# crawler2body.net
KiCad netlist of a schematic drawn in EAGLE
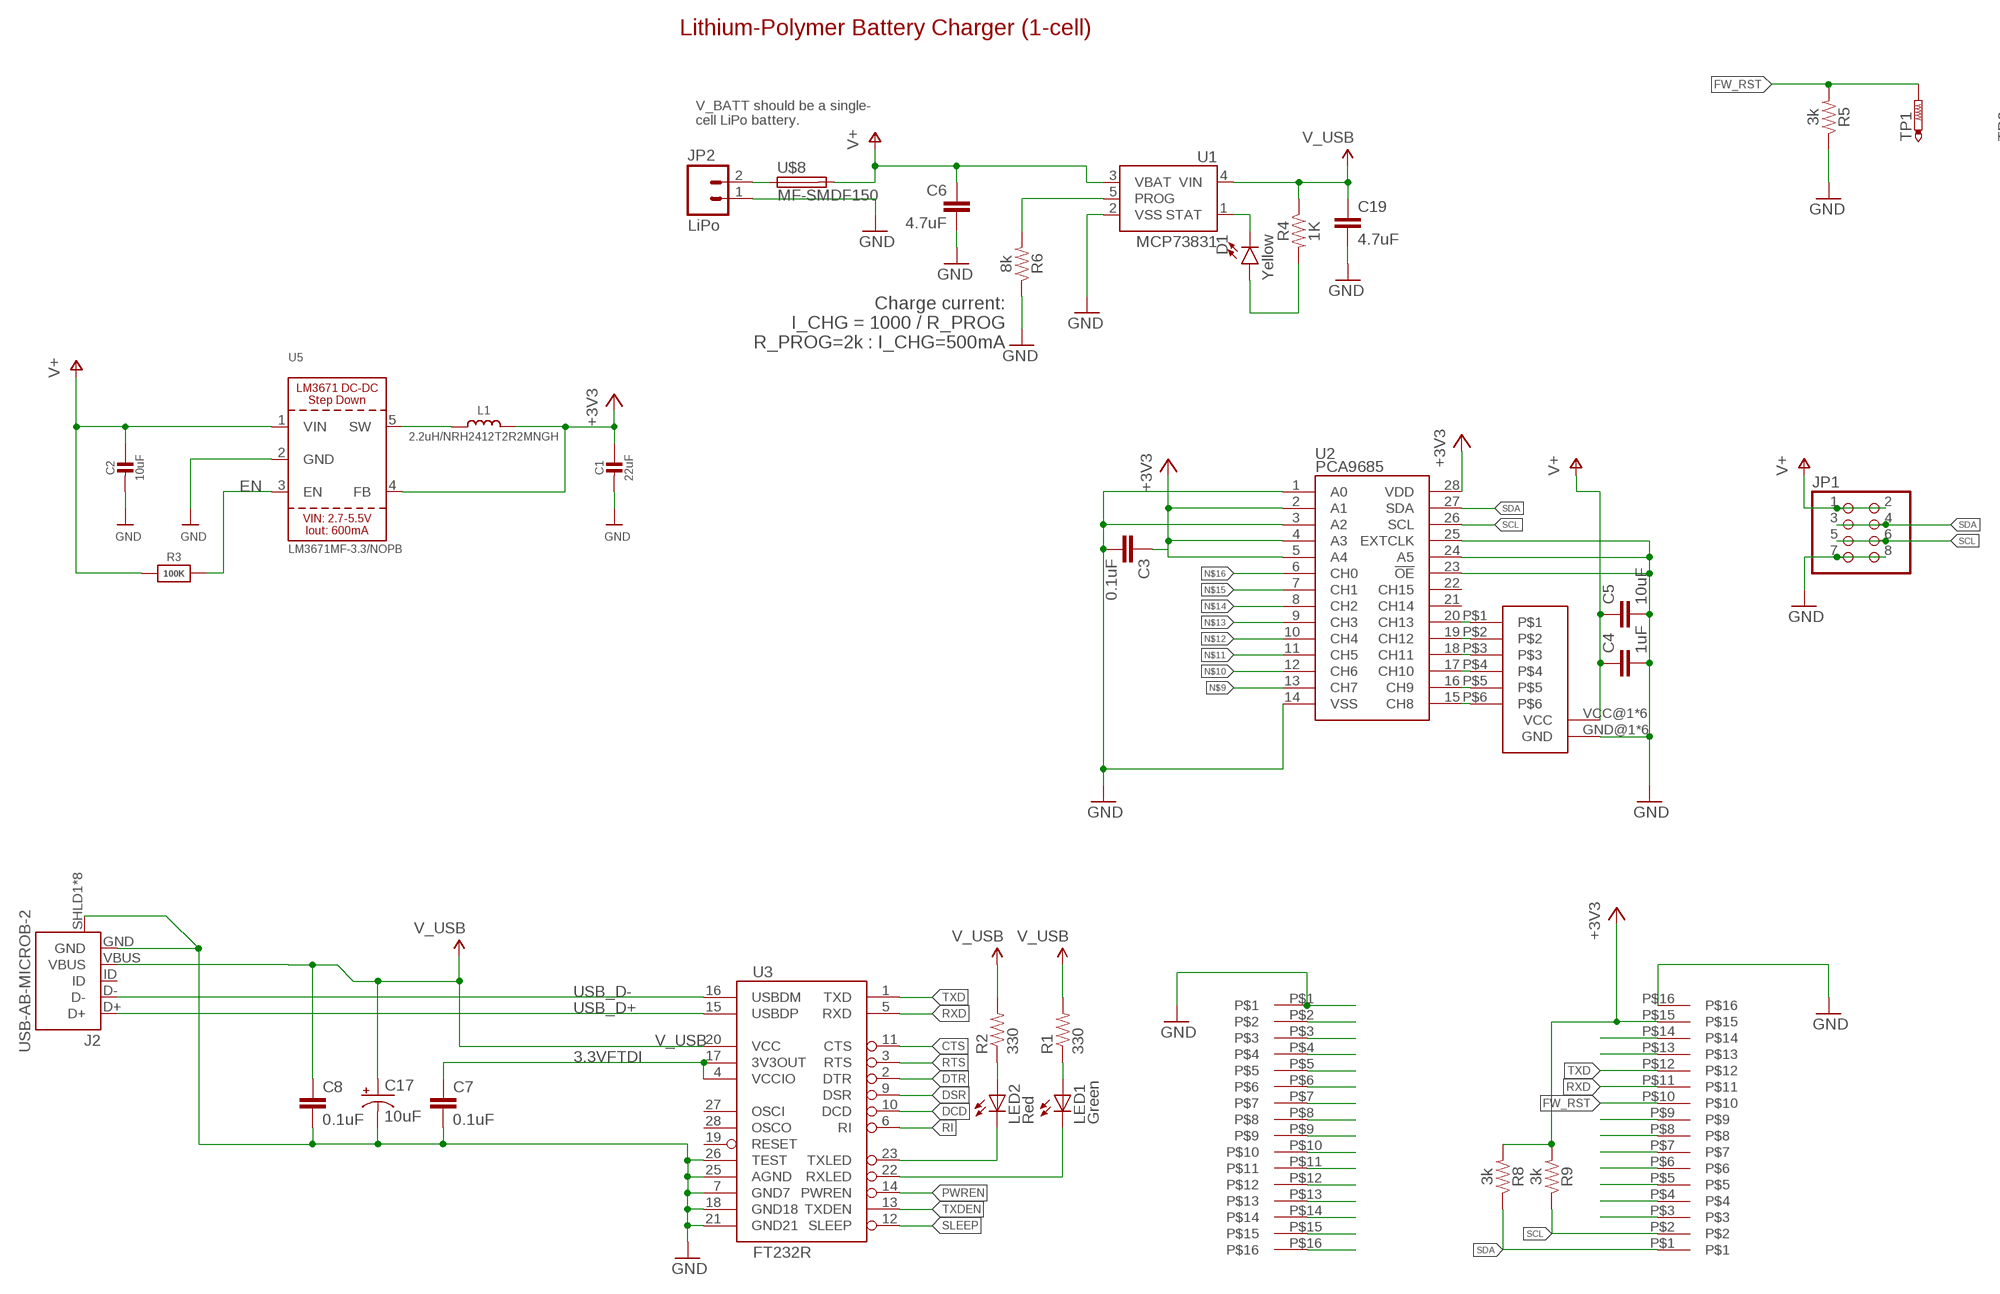
[diagram p0: schematic, sheet 1, part 1 of 2]
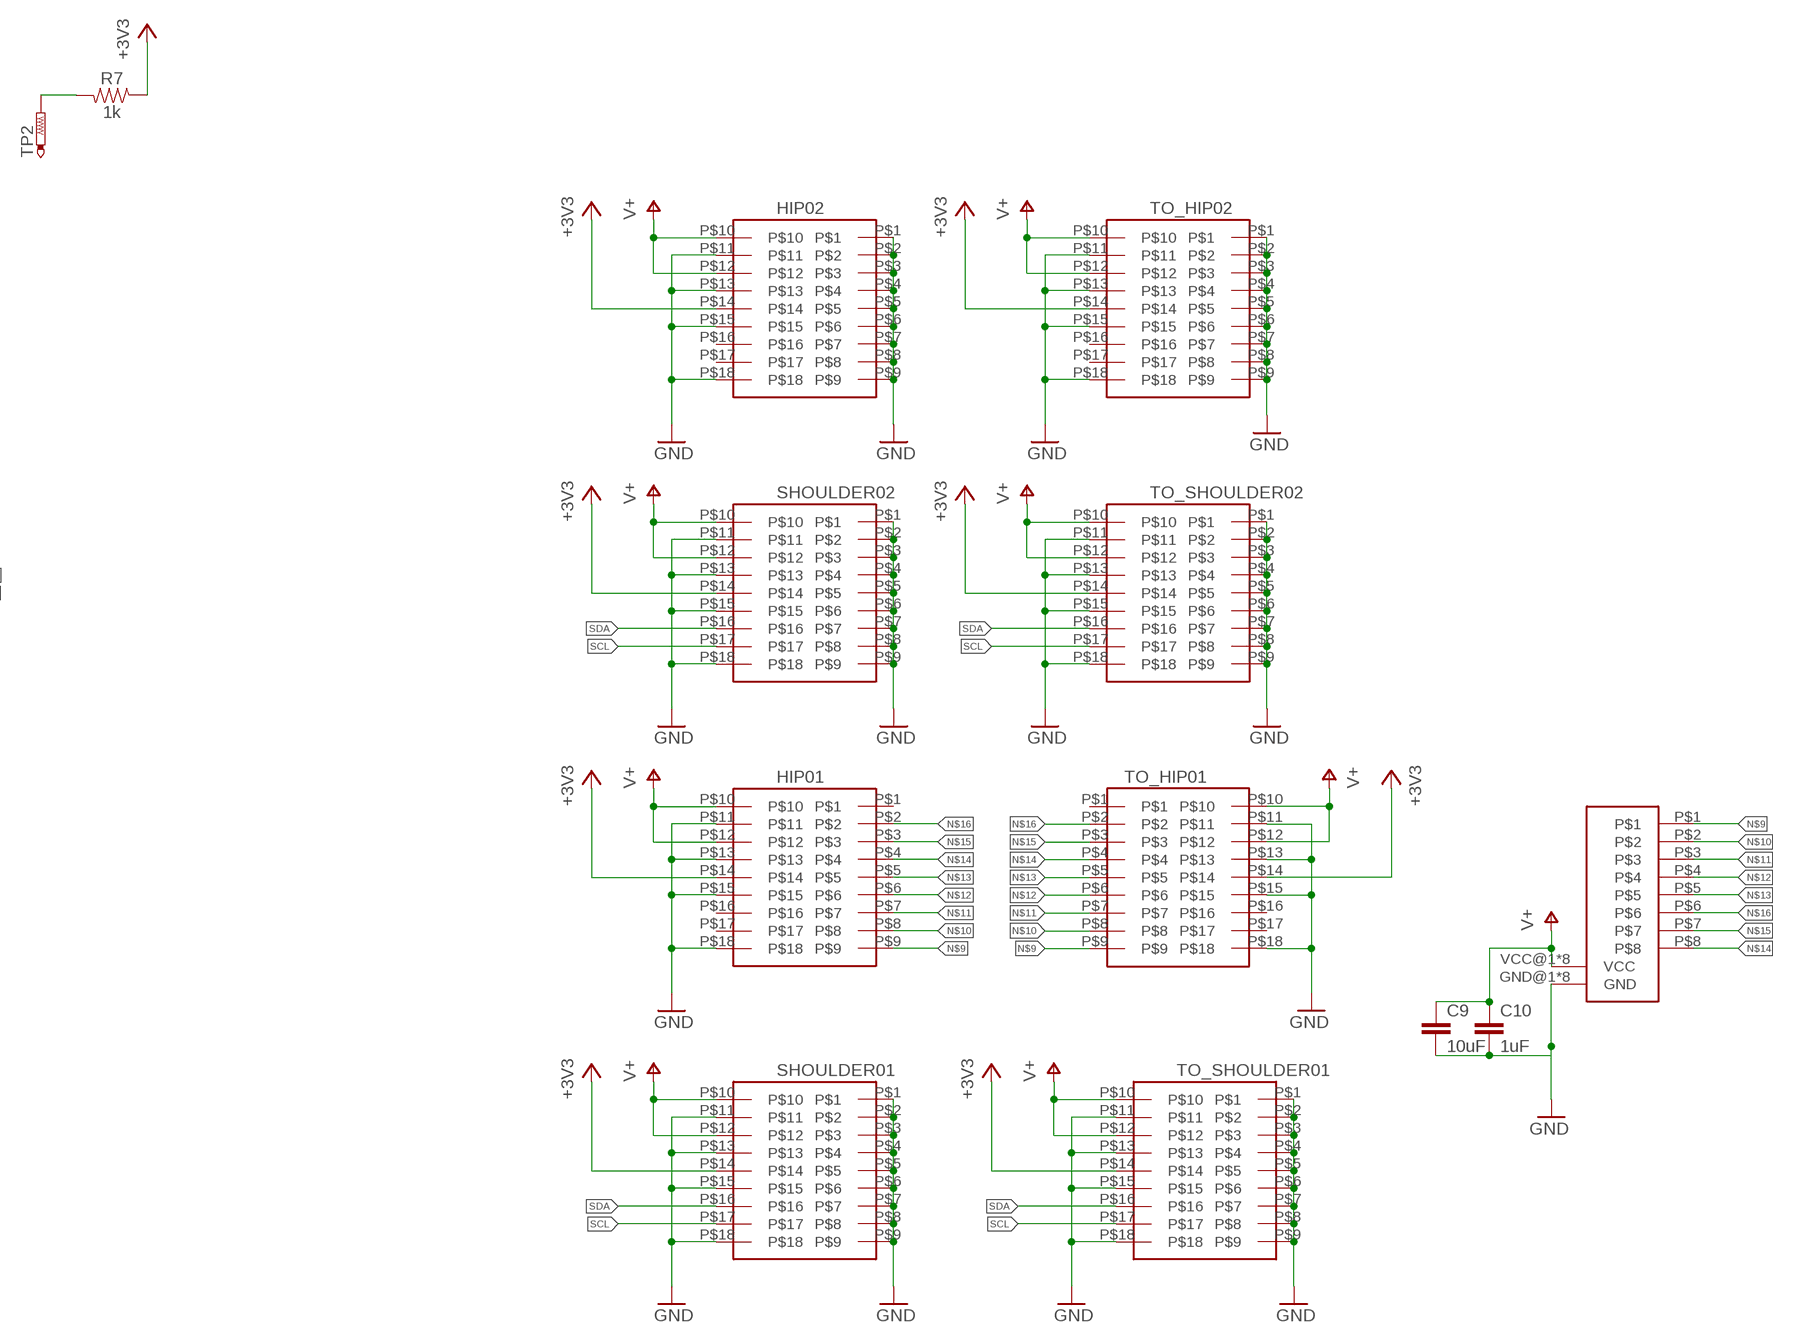
[diagram p1: schematic, sheet 1, part 2 of 2]

(export (version "E")
  (design (tool "Eeschema 10.0.6"))
  (components
    (comp (ref "C1")
      (value "22uF")
      (footprint "eagle-import:0805-NO")
      (libsource (lib "eagle-import") (part "CAP_CERAMIC0805-NOOUTLINE"))
    )
    (comp (ref "C2")
      (value "10uF")
      (footprint "eagle-import:0805-NO")
      (libsource (lib "eagle-import") (part "CAP_CERAMIC0805-NOOUTLINE"))
    )
    (comp (ref "C3")
      (value "0.1uF")
      (footprint "eagle-import:0603-CAP")
      (libsource (lib "eagle-import") (part "0.1UF-25V(+80/-20%)(0603)"))
    )
    (comp (ref "C4")
      (value "1uF")
      (footprint "eagle-import:C1210")
      (libsource (lib "eagle-import") (part "C-EUC1210"))
    )
    (comp (ref "C5")
      (value "10uF")
      (footprint "eagle-import:C1210")
      (libsource (lib "eagle-import") (part "C-EUC1210"))
    )
    (comp (ref "C6")
      (value "4.7uF")
      (footprint "eagle-import:0603")
      (libsource (lib "eagle-import") (part "4.7UF0603"))
    )
    (comp (ref "C7")
      (value "0.1uF")
      (footprint "eagle-import:0603-CAP")
      (libsource (lib "eagle-import") (part "0.1UF-25V(+80/-20%)(0603)"))
    )
    (comp (ref "C8")
      (value "0.1uF")
      (footprint "eagle-import:0603-CAP")
      (libsource (lib "eagle-import") (part "0.1UF-25V(+80/-20%)(0603)"))
    )
    (comp (ref "C9")
      (value "10uF")
      (footprint "eagle-import:C1210")
      (libsource (lib "eagle-import") (part "C-EUC1210"))
    )
    (comp (ref "C10")
      (value "1uF")
      (footprint "eagle-import:C1210")
      (libsource (lib "eagle-import") (part "C-EUC1210"))
    )
    (comp (ref "C17")
      (value "10uF")
      (footprint "eagle-import:EIA3216")
      (libsource (lib "eagle-import") (part "10UF-16V-10%(TANT)"))
    )
    (comp (ref "C19")
      (value "4.7uF")
      (footprint "eagle-import:0603")
      (libsource (lib "eagle-import") (part "4.7UF0603"))
    )
    (comp (ref "D1")
      (value "Yellow")
      (footprint "eagle-import:LED-0603")
      (libsource (lib "eagle-import") (part "LED-YELLOW0603"))
    )
    (comp (ref "HIP01")
      (value "BOARD2BOARD_SLOT")
      (footprint "eagle-import:BOARD2BOARD_SLOT")
      (libsource (lib "eagle-import") (part "BOARD2BOARD_SLOT"))
    )
    (comp (ref "HIP02")
      (value "BOARD2BOARD_SLOT")
      (footprint "eagle-import:BOARD2BOARD_SLOT")
      (libsource (lib "eagle-import") (part "BOARD2BOARD_SLOT"))
    )
    (comp (ref "J2")
      (value "USB-AB-MICROB-2")
      (footprint "eagle-import:USB-MICROB-10118194")
      (libsource (lib "eagle-import") (part "USB-AB-MICROB-2"))
    )
    (comp (ref "JP1")
      (value "PINHD-2X4")
      (footprint "eagle-import:2X04")
      (libsource (lib "eagle-import") (part "PINHD-2X4"))
    )
    (comp (ref "JP2")
      (value "LiPo")
      (footprint "eagle-import:JST-2-PTH-NS")
      (libsource (lib "eagle-import") (part "M02-JST-2-PTH-NO_SILK"))
    )
    (comp (ref "L1")
      (value "2.2uH/NRH2412T2R2MNGH")
      (footprint "eagle-import:INDUCTOR_TAIYOYUDEN_NRH2412T")
      (libsource (lib "eagle-import") (part "INDUCTORNRH2412T"))
    )
    (comp (ref "LED1")
      (value "Green")
      (footprint "eagle-import:LED-0603@1")
      (libsource (lib "eagle-import") (part "LED-GREEN0603"))
    )
    (comp (ref "LED2")
      (value "Red")
      (footprint "eagle-import:LED-0603@1")
      (libsource (lib "eagle-import") (part "LED-RED0603"))
    )
    (comp (ref "R1")
      (value "330")
      (footprint "eagle-import:0603-RES")
      (libsource (lib "eagle-import") (part "330OHM1/10W1%(0603)"))
    )
    (comp (ref "R2")
      (value "330")
      (footprint "eagle-import:0603-RES")
      (libsource (lib "eagle-import") (part "330OHM1/10W1%(0603)"))
    )
    (comp (ref "R3")
      (value "100K")
      (footprint "eagle-import:0805-NO")
      (libsource (lib "eagle-import") (part "RESISTOR0805_NOOUTLINE"))
    )
    (comp (ref "R4")
      (value "1K")
      (footprint "eagle-import:0603")
      (libsource (lib "eagle-import") (part "1KOHM-1/10W-1%(0603)"))
    )
    (comp (ref "R5")
      (value "3k")
      (footprint "eagle-import:0603")
      (libsource (lib "eagle-import") (part "2.0KOHM1/10W5%(0603)"))
    )
    (comp (ref "R6")
      (value "8k")
      (footprint "eagle-import:0603")
      (libsource (lib "eagle-import") (part "2.0KOHM1/10W5%(0603)"))
    )
    (comp (ref "R7")
      (value "1k")
      (footprint "eagle-import:0603")
      (libsource (lib "eagle-import") (part "2.0KOHM1/10W5%(0603)"))
    )
    (comp (ref "R8")
      (value "3k")
      (footprint "eagle-import:0603")
      (libsource (lib "eagle-import") (part "2.0KOHM1/10W5%(0603)"))
    )
    (comp (ref "R9")
      (value "3k")
      (footprint "eagle-import:0603")
      (libsource (lib "eagle-import") (part "2.0KOHM1/10W5%(0603)"))
    )
    (comp (ref "SHOULDER01")
      (value "BOARD2BOARD_SLOT")
      (footprint "eagle-import:BOARD2BOARD_SLOT")
      (libsource (lib "eagle-import") (part "BOARD2BOARD_SLOT"))
    )
    (comp (ref "SHOULDER02")
      (value "BOARD2BOARD_SLOT")
      (footprint "eagle-import:BOARD2BOARD_SLOT")
      (libsource (lib "eagle-import") (part "BOARD2BOARD_SLOT"))
    )
    (comp (ref "TO_HIP01")
      (value "BOARD2BOARD")
      (footprint "eagle-import:BOARD2BOARD")
      (libsource (lib "eagle-import") (part "BOARD2BOARD"))
    )
    (comp (ref "TO_HIP02")
      (value "BOARD2BOARD")
      (footprint "eagle-import:BOARD2BOARD")
      (libsource (lib "eagle-import") (part "BOARD2BOARD"))
    )
    (comp (ref "TO_SHOULDER01")
      (value "BOARD2BOARD")
      (footprint "eagle-import:BOARD2BOARD")
      (libsource (lib "eagle-import") (part "BOARD2BOARD"))
    )
    (comp (ref "TO_SHOULDER02")
      (value "BOARD2BOARD")
      (footprint "eagle-import:BOARD2BOARD")
      (libsource (lib "eagle-import") (part "BOARD2BOARD"))
    )
    (comp (ref "TP1")
      (value "PTR1TP15SQ")
      (footprint "eagle-import:TP15SQ")
      (libsource (lib "eagle-import") (part "PTR1TP15SQ"))
    )
    (comp (ref "TP2")
      (value "PTR1TP15SQ")
      (footprint "eagle-import:TP15SQ")
      (libsource (lib "eagle-import") (part "PTR1TP15SQ"))
    )
    (comp (ref "U$1")
      (value "SPLITPAC_OMEGA2")
      (footprint "eagle-import:SPLITTED_OMEGA2")
      (libsource (lib "eagle-import") (part "SPLITPAC_OMEGA2"))
    )
    (comp (ref "U$2")
      (value "SPLITPAC_OMEGA2")
      (footprint "eagle-import:SPLITTED_OMEGA2")
      (libsource (lib "eagle-import") (part "SPLITPAC_OMEGA2"))
    )
    (comp (ref "U$3")
      (value "RC8CHAN")
      (footprint "eagle-import:RC8CHAN")
      (libsource (lib "eagle-import") (part "RC8CHAN"))
    )
    (comp (ref "U$4")
      (value "RC6CHAN")
      (footprint "eagle-import:RC6CHAN")
      (libsource (lib "eagle-import") (part "RC6CHAN"))
    )
    (comp (ref "U$8")
      (value "MF-SMDF150")
      (footprint "eagle-import:MF-SMDF050")
      (libsource (lib "eagle-import") (part "MF-SMDF150"))
    )
    (comp (ref "U1")
      (value "MCP73831")
      (footprint "eagle-import:SOT23-5")
      (libsource (lib "eagle-import") (part "MCP73831"))
    )
    (comp (ref "U2")
      (value "PCA9685")
      (footprint "eagle-import:TSSOP-28_4MM")
      (libsource (lib "eagle-import") (part "PCA9685"))
    )
    (comp (ref "U3")
      (value "FT232R")
      (footprint "eagle-import:SSOP28DB")
      (libsource (lib "eagle-import") (part "FT232RLSSOP"))
    )
    (comp (ref "U5")
      (value "LM3671MF-3.3/NOPB")
      (footprint "eagle-import:SOT23-5")
      (libsource (lib "eagle-import") (part "VREG_LM3671"))
    )
  )
  (nets
    (net (code "1") (name "+3V3") (class "Default")
      (node (ref "C1") (pin "1") (pinfunction "1_1") (pintype "passive"))
      (node (ref "C3") (pin "1") (pinfunction "1_1") (pintype "passive"))
      (node (ref "HIP01") (pin "P$14") (pinfunction "P$14_P$14") (pintype "bidirectional"))
      (node (ref "HIP02") (pin "P$14") (pinfunction "P$14_P$14") (pintype "bidirectional"))
      (node (ref "L1") (pin "2") (pinfunction "2_2") (pintype "passive"))
      (node (ref "R7") (pin "1") (pinfunction "1_1") (pintype "passive"))
      (node (ref "R8") (pin "2") (pinfunction "2_2") (pintype "passive"))
      (node (ref "R9") (pin "2") (pinfunction "2_2") (pintype "passive"))
      (node (ref "SHOULDER01") (pin "P$14") (pinfunction "P$14_P$14") (pintype "bidirectional"))
      (node (ref "SHOULDER02") (pin "P$14") (pinfunction "P$14_P$14") (pintype "bidirectional"))
      (node (ref "TO_HIP01") (pin "P$14") (pinfunction "P$14_P$14") (pintype "bidirectional"))
      (node (ref "TO_HIP02") (pin "P$14") (pinfunction "P$14_P$14") (pintype "bidirectional"))
      (node (ref "TO_SHOULDER01") (pin "P$14") (pinfunction "P$14_P$14") (pintype "bidirectional"))
      (node (ref "TO_SHOULDER02") (pin "P$14") (pinfunction "P$14_P$14") (pintype "bidirectional"))
      (node (ref "U$2") (pin "P$15") (pinfunction "P$15_P$15") (pintype "bidirectional"))
      (node (ref "U2") (pin "2") (pinfunction "A1_2") (pintype "bidirectional"))
      (node (ref "U2") (pin "28") (pinfunction "VDD_28") (pintype "bidirectional"))
      (node (ref "U2") (pin "4") (pinfunction "A3_4") (pintype "bidirectional"))
      (node (ref "U2") (pin "5") (pinfunction "A4_5") (pintype "bidirectional"))
      (node (ref "U5") (pin "4") (pinfunction "FB_4") (pintype "power_in"))
    )
    (net (code "2") (name "/3.3VFTDI") (class "Default")
      (node (ref "C7") (pin "1") (pinfunction "1_1") (pintype "passive"))
      (node (ref "U3") (pin "17") (pinfunction "3V3OUT_17") (pintype "output"))
      (node (ref "U3") (pin "4") (pinfunction "VCCIO_4") (pintype "power_in"))
    )
    (net (code "3") (name "/EN") (class "Default")
      (node (ref "R3") (pin "2") (pinfunction "2_2") (pintype "passive"))
      (node (ref "U5") (pin "3") (pinfunction "EN_3") (pintype "input"))
    )
    (net (code "4") (name "/USB_D+") (class "Default")
      (node (ref "J2") (pin "D+") (pinfunction "D+_D+") (pintype "bidirectional"))
      (node (ref "U3") (pin "15") (pinfunction "USBDP_15") (pintype "bidirectional"))
    )
    (net (code "5") (name "/USB_D-") (class "Default")
      (node (ref "J2") (pin "D-") (pinfunction "D-_D-") (pintype "bidirectional"))
      (node (ref "U3") (pin "16") (pinfunction "USBDM_16") (pintype "bidirectional"))
    )
    (net (code "6") (name "CTS") (class "Default")
      (node (ref "U3") (pin "11") (pinfunction "CTS_11") (pintype "input"))
    )
    (net (code "7") (name "DCD") (class "Default")
      (node (ref "U3") (pin "10") (pinfunction "DCD_10") (pintype "input"))
    )
    (net (code "8") (name "DSR") (class "Default")
      (node (ref "U3") (pin "9") (pinfunction "DSR_9") (pintype "input"))
    )
    (net (code "9") (name "DTR") (class "Default")
      (node (ref "U3") (pin "2") (pinfunction "DTR_2") (pintype "output"))
    )
    (net (code "10") (name "FW_RST") (class "Default")
      (node (ref "R5") (pin "2") (pinfunction "2_2") (pintype "passive"))
      (node (ref "TP1") (pin "TP") (pinfunction "TP_TP") (pintype "input"))
      (node (ref "U$2") (pin "P$10") (pinfunction "P$10_P$10") (pintype "bidirectional"))
    )
    (net (code "11") (name "GND") (class "Default")
      (node (ref "C1") (pin "2") (pinfunction "2_2") (pintype "passive"))
      (node (ref "C10") (pin "2") (pinfunction "2_2") (pintype "passive"))
      (node (ref "C17") (pin "C") (pinfunction "-_C") (pintype "passive"))
      (node (ref "C19") (pin "2") (pinfunction "2_2") (pintype "passive"))
      (node (ref "C2") (pin "2") (pinfunction "2_2") (pintype "passive"))
      (node (ref "C3") (pin "2") (pinfunction "2_2") (pintype "passive"))
      (node (ref "C4") (pin "2") (pinfunction "2_2") (pintype "passive"))
      (node (ref "C5") (pin "2") (pinfunction "2_2") (pintype "passive"))
      (node (ref "C6") (pin "2") (pinfunction "2_2") (pintype "passive"))
      (node (ref "C7") (pin "2") (pinfunction "2_2") (pintype "passive"))
      (node (ref "C8") (pin "2") (pinfunction "2_2") (pintype "passive"))
      (node (ref "C9") (pin "2") (pinfunction "2_2") (pintype "passive"))
      (node (ref "HIP01") (pin "P$11") (pinfunction "P$11_P$11") (pintype "bidirectional"))
      (node (ref "HIP01") (pin "P$13") (pinfunction "P$13_P$13") (pintype "bidirectional"))
      (node (ref "HIP01") (pin "P$15") (pinfunction "P$15_P$15") (pintype "bidirectional"))
      (node (ref "HIP01") (pin "P$18") (pinfunction "P$18_P$18") (pintype "bidirectional"))
      (node (ref "HIP02") (pin "P$1") (pinfunction "P$1_P$1") (pintype "bidirectional"))
      (node (ref "HIP02") (pin "P$11") (pinfunction "P$11_P$11") (pintype "bidirectional"))
      (node (ref "HIP02") (pin "P$13") (pinfunction "P$13_P$13") (pintype "bidirectional"))
      (node (ref "HIP02") (pin "P$15") (pinfunction "P$15_P$15") (pintype "bidirectional"))
      (node (ref "HIP02") (pin "P$18") (pinfunction "P$18_P$18") (pintype "bidirectional"))
      (node (ref "HIP02") (pin "P$2") (pinfunction "P$2_P$2") (pintype "bidirectional"))
      (node (ref "HIP02") (pin "P$3") (pinfunction "P$3_P$3") (pintype "bidirectional"))
      (node (ref "HIP02") (pin "P$4") (pinfunction "P$4_P$4") (pintype "bidirectional"))
      (node (ref "HIP02") (pin "P$5") (pinfunction "P$5_P$5") (pintype "bidirectional"))
      (node (ref "HIP02") (pin "P$6") (pinfunction "P$6_P$6") (pintype "bidirectional"))
      (node (ref "HIP02") (pin "P$7") (pinfunction "P$7_P$7") (pintype "bidirectional"))
      (node (ref "HIP02") (pin "P$8") (pinfunction "P$8_P$8") (pintype "bidirectional"))
      (node (ref "HIP02") (pin "P$9") (pinfunction "P$9_P$9") (pintype "bidirectional"))
      (node (ref "J2") (pin "GND") (pinfunction "GND_GND") (pintype "power_in"))
      (node (ref "J2") (pin "SHLD1") (pinfunction "SHIELD_SHLD1") (pintype "passive"))
      (node (ref "J2") (pin "SHLD2") (pinfunction "SHIELD_SHLD2") (pintype "passive"))
      (node (ref "J2") (pin "SHLD3") (pinfunction "SHIELD_SHLD3") (pintype "passive"))
      (node (ref "J2") (pin "SHLD4") (pinfunction "SHIELD_SHLD4") (pintype "passive"))
      (node (ref "J2") (pin "SHLD5") (pinfunction "SHIELD_SHLD5") (pintype "passive"))
      (node (ref "J2") (pin "SHLD6") (pinfunction "SHIELD_SHLD6") (pintype "passive"))
      (node (ref "J2") (pin "SHLD7") (pinfunction "SHIELD_SHLD7") (pintype "passive"))
      (node (ref "J2") (pin "SHLD8") (pinfunction "SHIELD_SHLD8") (pintype "passive"))
      (node (ref "JP1") (pin "7") (pinfunction "7_7") (pintype "passive"))
      (node (ref "JP1") (pin "8") (pinfunction "8_8") (pintype "passive"))
      (node (ref "JP2") (pin "1") (pinfunction "1_1") (pintype "passive"))
      (node (ref "R5") (pin "1") (pinfunction "1_1") (pintype "passive"))
      (node (ref "R6") (pin "1") (pinfunction "1_1") (pintype "passive"))
      (node (ref "SHOULDER01") (pin "P$1") (pinfunction "P$1_P$1") (pintype "bidirectional"))
      (node (ref "SHOULDER01") (pin "P$11") (pinfunction "P$11_P$11") (pintype "bidirectional"))
      (node (ref "SHOULDER01") (pin "P$13") (pinfunction "P$13_P$13") (pintype "bidirectional"))
      (node (ref "SHOULDER01") (pin "P$15") (pinfunction "P$15_P$15") (pintype "bidirectional"))
      (node (ref "SHOULDER01") (pin "P$18") (pinfunction "P$18_P$18") (pintype "bidirectional"))
      (node (ref "SHOULDER01") (pin "P$2") (pinfunction "P$2_P$2") (pintype "bidirectional"))
      (node (ref "SHOULDER01") (pin "P$3") (pinfunction "P$3_P$3") (pintype "bidirectional"))
      (node (ref "SHOULDER01") (pin "P$4") (pinfunction "P$4_P$4") (pintype "bidirectional"))
      (node (ref "SHOULDER01") (pin "P$5") (pinfunction "P$5_P$5") (pintype "bidirectional"))
      (node (ref "SHOULDER01") (pin "P$6") (pinfunction "P$6_P$6") (pintype "bidirectional"))
      (node (ref "SHOULDER01") (pin "P$7") (pinfunction "P$7_P$7") (pintype "bidirectional"))
      (node (ref "SHOULDER01") (pin "P$8") (pinfunction "P$8_P$8") (pintype "bidirectional"))
      (node (ref "SHOULDER01") (pin "P$9") (pinfunction "P$9_P$9") (pintype "bidirectional"))
      (node (ref "SHOULDER02") (pin "P$1") (pinfunction "P$1_P$1") (pintype "bidirectional"))
      (node (ref "SHOULDER02") (pin "P$11") (pinfunction "P$11_P$11") (pintype "bidirectional"))
      (node (ref "SHOULDER02") (pin "P$13") (pinfunction "P$13_P$13") (pintype "bidirectional"))
      (node (ref "SHOULDER02") (pin "P$15") (pinfunction "P$15_P$15") (pintype "bidirectional"))
      (node (ref "SHOULDER02") (pin "P$18") (pinfunction "P$18_P$18") (pintype "bidirectional"))
      (node (ref "SHOULDER02") (pin "P$2") (pinfunction "P$2_P$2") (pintype "bidirectional"))
      (node (ref "SHOULDER02") (pin "P$3") (pinfunction "P$3_P$3") (pintype "bidirectional"))
      (node (ref "SHOULDER02") (pin "P$4") (pinfunction "P$4_P$4") (pintype "bidirectional"))
      (node (ref "SHOULDER02") (pin "P$5") (pinfunction "P$5_P$5") (pintype "bidirectional"))
      (node (ref "SHOULDER02") (pin "P$6") (pinfunction "P$6_P$6") (pintype "bidirectional"))
      (node (ref "SHOULDER02") (pin "P$7") (pinfunction "P$7_P$7") (pintype "bidirectional"))
      (node (ref "SHOULDER02") (pin "P$8") (pinfunction "P$8_P$8") (pintype "bidirectional"))
      (node (ref "SHOULDER02") (pin "P$9") (pinfunction "P$9_P$9") (pintype "bidirectional"))
      (node (ref "TO_HIP01") (pin "P$11") (pinfunction "P$11_P$11") (pintype "bidirectional"))
      (node (ref "TO_HIP01") (pin "P$13") (pinfunction "P$13_P$13") (pintype "bidirectional"))
      (node (ref "TO_HIP01") (pin "P$15") (pinfunction "P$15_P$15") (pintype "bidirectional"))
      (node (ref "TO_HIP01") (pin "P$18") (pinfunction "P$18_P$18") (pintype "bidirectional"))
      (node (ref "TO_HIP02") (pin "P$1") (pinfunction "P$1_P$1") (pintype "bidirectional"))
      (node (ref "TO_HIP02") (pin "P$11") (pinfunction "P$11_P$11") (pintype "bidirectional"))
      (node (ref "TO_HIP02") (pin "P$13") (pinfunction "P$13_P$13") (pintype "bidirectional"))
      (node (ref "TO_HIP02") (pin "P$15") (pinfunction "P$15_P$15") (pintype "bidirectional"))
      (node (ref "TO_HIP02") (pin "P$18") (pinfunction "P$18_P$18") (pintype "bidirectional"))
      (node (ref "TO_HIP02") (pin "P$2") (pinfunction "P$2_P$2") (pintype "bidirectional"))
      (node (ref "TO_HIP02") (pin "P$3") (pinfunction "P$3_P$3") (pintype "bidirectional"))
      (node (ref "TO_HIP02") (pin "P$4") (pinfunction "P$4_P$4") (pintype "bidirectional"))
      (node (ref "TO_HIP02") (pin "P$5") (pinfunction "P$5_P$5") (pintype "bidirectional"))
      (node (ref "TO_HIP02") (pin "P$6") (pinfunction "P$6_P$6") (pintype "bidirectional"))
      (node (ref "TO_HIP02") (pin "P$7") (pinfunction "P$7_P$7") (pintype "bidirectional"))
      (node (ref "TO_HIP02") (pin "P$8") (pinfunction "P$8_P$8") (pintype "bidirectional"))
      (node (ref "TO_HIP02") (pin "P$9") (pinfunction "P$9_P$9") (pintype "bidirectional"))
      (node (ref "TO_SHOULDER01") (pin "P$1") (pinfunction "P$1_P$1") (pintype "bidirectional"))
      (node (ref "TO_SHOULDER01") (pin "P$11") (pinfunction "P$11_P$11") (pintype "bidirectional"))
      (node (ref "TO_SHOULDER01") (pin "P$13") (pinfunction "P$13_P$13") (pintype "bidirectional"))
      (node (ref "TO_SHOULDER01") (pin "P$15") (pinfunction "P$15_P$15") (pintype "bidirectional"))
      (node (ref "TO_SHOULDER01") (pin "P$18") (pinfunction "P$18_P$18") (pintype "bidirectional"))
      (node (ref "TO_SHOULDER01") (pin "P$2") (pinfunction "P$2_P$2") (pintype "bidirectional"))
      (node (ref "TO_SHOULDER01") (pin "P$3") (pinfunction "P$3_P$3") (pintype "bidirectional"))
      (node (ref "TO_SHOULDER01") (pin "P$4") (pinfunction "P$4_P$4") (pintype "bidirectional"))
      (node (ref "TO_SHOULDER01") (pin "P$5") (pinfunction "P$5_P$5") (pintype "bidirectional"))
      (node (ref "TO_SHOULDER01") (pin "P$6") (pinfunction "P$6_P$6") (pintype "bidirectional"))
      (node (ref "TO_SHOULDER01") (pin "P$7") (pinfunction "P$7_P$7") (pintype "bidirectional"))
      (node (ref "TO_SHOULDER01") (pin "P$8") (pinfunction "P$8_P$8") (pintype "bidirectional"))
      (node (ref "TO_SHOULDER01") (pin "P$9") (pinfunction "P$9_P$9") (pintype "bidirectional"))
      (node (ref "TO_SHOULDER02") (pin "P$1") (pinfunction "P$1_P$1") (pintype "bidirectional"))
      (node (ref "TO_SHOULDER02") (pin "P$11") (pinfunction "P$11_P$11") (pintype "bidirectional"))
      (node (ref "TO_SHOULDER02") (pin "P$13") (pinfunction "P$13_P$13") (pintype "bidirectional"))
      (node (ref "TO_SHOULDER02") (pin "P$15") (pinfunction "P$15_P$15") (pintype "bidirectional"))
      (node (ref "TO_SHOULDER02") (pin "P$18") (pinfunction "P$18_P$18") (pintype "bidirectional"))
      (node (ref "TO_SHOULDER02") (pin "P$2") (pinfunction "P$2_P$2") (pintype "bidirectional"))
      (node (ref "TO_SHOULDER02") (pin "P$3") (pinfunction "P$3_P$3") (pintype "bidirectional"))
      (node (ref "TO_SHOULDER02") (pin "P$4") (pinfunction "P$4_P$4") (pintype "bidirectional"))
      (node (ref "TO_SHOULDER02") (pin "P$5") (pinfunction "P$5_P$5") (pintype "bidirectional"))
      (node (ref "TO_SHOULDER02") (pin "P$6") (pinfunction "P$6_P$6") (pintype "bidirectional"))
      (node (ref "TO_SHOULDER02") (pin "P$7") (pinfunction "P$7_P$7") (pintype "bidirectional"))
      (node (ref "TO_SHOULDER02") (pin "P$8") (pinfunction "P$8_P$8") (pintype "bidirectional"))
      (node (ref "TO_SHOULDER02") (pin "P$9") (pinfunction "P$9_P$9") (pintype "bidirectional"))
      (node (ref "U$1") (pin "P$1") (pinfunction "P$1_P$1") (pintype "bidirectional"))
      (node (ref "U$2") (pin "P$16") (pinfunction "P$16_P$16") (pintype "bidirectional"))
      (node (ref "U$3") (pin "GND@1") (pinfunction "GND_GND@1") (pintype "power_in"))
      (node (ref "U$3") (pin "GND@2") (pinfunction "GND_GND@2") (pintype "power_in"))
      (node (ref "U$3") (pin "GND@3") (pinfunction "GND_GND@3") (pintype "power_in"))
      (node (ref "U$3") (pin "GND@4") (pinfunction "GND_GND@4") (pintype "power_in"))
      (node (ref "U$3") (pin "GND@5") (pinfunction "GND_GND@5") (pintype "power_in"))
      (node (ref "U$3") (pin "GND@6") (pinfunction "GND_GND@6") (pintype "power_in"))
      (node (ref "U$3") (pin "GND@7") (pinfunction "GND_GND@7") (pintype "power_in"))
      (node (ref "U$3") (pin "GND@8") (pinfunction "GND_GND@8") (pintype "power_in"))
      (node (ref "U$4") (pin "GND@1") (pinfunction "GND_GND@1") (pintype "power_in"))
      (node (ref "U$4") (pin "GND@2") (pinfunction "GND_GND@2") (pintype "power_in"))
      (node (ref "U$4") (pin "GND@3") (pinfunction "GND_GND@3") (pintype "power_in"))
      (node (ref "U$4") (pin "GND@4") (pinfunction "GND_GND@4") (pintype "power_in"))
      (node (ref "U$4") (pin "GND@5") (pinfunction "GND_GND@5") (pintype "power_in"))
      (node (ref "U$4") (pin "GND@6") (pinfunction "GND_GND@6") (pintype "power_in"))
      (node (ref "U1") (pin "2") (pinfunction "VSS_2") (pintype "power_in"))
      (node (ref "U2") (pin "1") (pinfunction "A0_1") (pintype "bidirectional"))
      (node (ref "U2") (pin "14") (pinfunction "VSS_14") (pintype "bidirectional"))
      (node (ref "U2") (pin "23") (pinfunction "~{OE}_23") (pintype "bidirectional"))
      (node (ref "U2") (pin "24") (pinfunction "A5_24") (pintype "bidirectional"))
      (node (ref "U2") (pin "25") (pinfunction "EXTCLK_25") (pintype "bidirectional"))
      (node (ref "U2") (pin "3") (pinfunction "A2_3") (pintype "bidirectional"))
      (node (ref "U3") (pin "18") (pinfunction "GND18_18") (pintype "power_in"))
      (node (ref "U3") (pin "21") (pinfunction "GND21_21") (pintype "power_in"))
      (node (ref "U3") (pin "25") (pinfunction "AGND_25") (pintype "power_in"))
      (node (ref "U3") (pin "26") (pinfunction "TEST_26") (pintype "input"))
      (node (ref "U3") (pin "7") (pinfunction "GND7_7") (pintype "power_in"))
      (node (ref "U5") (pin "2") (pinfunction "GND_2") (pintype "power_in"))
    )
    (net (code "12") (name "N$9") (class "Default")
      (node (ref "HIP01") (pin "P$9") (pinfunction "P$9_P$9") (pintype "bidirectional"))
      (node (ref "TO_HIP01") (pin "P$9") (pinfunction "P$9_P$9") (pintype "bidirectional"))
      (node (ref "U$3") (pin "P$1") (pinfunction "P$1_P$1") (pintype "bidirectional"))
      (node (ref "U2") (pin "13") (pinfunction "CH7_13") (pintype "bidirectional"))
    )
    (net (code "13") (name "N$10") (class "Default")
      (node (ref "HIP01") (pin "P$8") (pinfunction "P$8_P$8") (pintype "bidirectional"))
      (node (ref "TO_HIP01") (pin "P$8") (pinfunction "P$8_P$8") (pintype "bidirectional"))
      (node (ref "U$3") (pin "P$2") (pinfunction "P$2_P$2") (pintype "bidirectional"))
      (node (ref "U2") (pin "12") (pinfunction "CH6_12") (pintype "bidirectional"))
    )
    (net (code "14") (name "N$11") (class "Default")
      (node (ref "HIP01") (pin "P$7") (pinfunction "P$7_P$7") (pintype "bidirectional"))
      (node (ref "TO_HIP01") (pin "P$7") (pinfunction "P$7_P$7") (pintype "bidirectional"))
      (node (ref "U$3") (pin "P$3") (pinfunction "P$3_P$3") (pintype "bidirectional"))
      (node (ref "U2") (pin "11") (pinfunction "CH5_11") (pintype "bidirectional"))
    )
    (net (code "15") (name "N$12") (class "Default")
      (node (ref "HIP01") (pin "P$6") (pinfunction "P$6_P$6") (pintype "bidirectional"))
      (node (ref "TO_HIP01") (pin "P$6") (pinfunction "P$6_P$6") (pintype "bidirectional"))
      (node (ref "U$3") (pin "P$4") (pinfunction "P$4_P$4") (pintype "bidirectional"))
      (node (ref "U2") (pin "10") (pinfunction "CH4_10") (pintype "bidirectional"))
    )
    (net (code "16") (name "N$13") (class "Default")
      (node (ref "HIP01") (pin "P$5") (pinfunction "P$5_P$5") (pintype "bidirectional"))
      (node (ref "TO_HIP01") (pin "P$5") (pinfunction "P$5_P$5") (pintype "bidirectional"))
      (node (ref "U$3") (pin "P$5") (pinfunction "P$5_P$5") (pintype "bidirectional"))
      (node (ref "U2") (pin "9") (pinfunction "CH3_9") (pintype "bidirectional"))
    )
    (net (code "17") (name "N$14") (class "Default")
      (node (ref "HIP01") (pin "P$4") (pinfunction "P$4_P$4") (pintype "bidirectional"))
      (node (ref "TO_HIP01") (pin "P$4") (pinfunction "P$4_P$4") (pintype "bidirectional"))
      (node (ref "U$3") (pin "P$8") (pinfunction "P$8_P$8") (pintype "bidirectional"))
      (node (ref "U2") (pin "8") (pinfunction "CH2_8") (pintype "bidirectional"))
    )
    (net (code "18") (name "N$15") (class "Default")
      (node (ref "HIP01") (pin "P$3") (pinfunction "P$3_P$3") (pintype "bidirectional"))
      (node (ref "TO_HIP01") (pin "P$3") (pinfunction "P$3_P$3") (pintype "bidirectional"))
      (node (ref "U$3") (pin "P$7") (pinfunction "P$7_P$7") (pintype "bidirectional"))
      (node (ref "U2") (pin "7") (pinfunction "CH1_7") (pintype "bidirectional"))
    )
    (net (code "19") (name "N$16") (class "Default")
      (node (ref "HIP01") (pin "P$2") (pinfunction "P$2_P$2") (pintype "bidirectional"))
      (node (ref "TO_HIP01") (pin "P$2") (pinfunction "P$2_P$2") (pintype "bidirectional"))
      (node (ref "U$3") (pin "P$6") (pinfunction "P$6_P$6") (pintype "bidirectional"))
      (node (ref "U2") (pin "6") (pinfunction "CH0_6") (pintype "bidirectional"))
    )
    (net (code "20") (name "Net-(D1-PadA)") (class "Default")
      (node (ref "D1") (pin "A") (pinfunction "A_A") (pintype "passive"))
      (node (ref "R4") (pin "2") (pinfunction "2_2") (pintype "passive"))
    )
    (net (code "21") (name "Net-(JP2-Pad2)") (class "Default")
      (node (ref "JP2") (pin "2") (pinfunction "2_2") (pintype "passive"))
      (node (ref "U$8") (pin "1") (pinfunction "1_1") (pintype "passive"))
    )
    (net (code "22") (name "Net-(LED1-PadA)") (class "Default")
      (node (ref "LED1") (pin "A") (pinfunction "A_A") (pintype "passive"))
      (node (ref "R1") (pin "1") (pinfunction "1_1") (pintype "passive"))
    )
    (net (code "23") (name "Net-(LED2-PadA)") (class "Default")
      (node (ref "LED2") (pin "A") (pinfunction "A_A") (pintype "passive"))
      (node (ref "R2") (pin "1") (pinfunction "1_1") (pintype "passive"))
    )
    (net (code "24") (name "Net-(R7-Pad2)") (class "Default")
      (node (ref "R7") (pin "2") (pinfunction "2_2") (pintype "passive"))
      (node (ref "TP2") (pin "TP") (pinfunction "TP_TP") (pintype "input"))
    )
    (net (code "25") (name "Net-(U1-PROG)") (class "Default")
      (node (ref "R6") (pin "2") (pinfunction "2_2") (pintype "passive"))
      (node (ref "U1") (pin "5") (pinfunction "PROG_5") (pintype "input"))
    )
    (net (code "26") (name "Net-(U1-STAT)") (class "Default")
      (node (ref "D1") (pin "C") (pinfunction "C_C") (pintype "passive"))
      (node (ref "U1") (pin "1") (pinfunction "STAT_1") (pintype "output"))
    )
    (net (code "27") (name "Net-(U2-CH8)") (class "Default")
      (node (ref "U$4") (pin "P$6") (pinfunction "P$6_P$6") (pintype "bidirectional"))
      (node (ref "U2") (pin "15") (pinfunction "CH8_15") (pintype "bidirectional"))
    )
    (net (code "28") (name "Net-(U2-CH9)") (class "Default")
      (node (ref "U$4") (pin "P$5") (pinfunction "P$5_P$5") (pintype "bidirectional"))
      (node (ref "U2") (pin "16") (pinfunction "CH9_16") (pintype "bidirectional"))
    )
    (net (code "29") (name "Net-(U2-CH10)") (class "Default")
      (node (ref "U$4") (pin "P$4") (pinfunction "P$4_P$4") (pintype "bidirectional"))
      (node (ref "U2") (pin "17") (pinfunction "CH10_17") (pintype "bidirectional"))
    )
    (net (code "30") (name "Net-(U2-CH11)") (class "Default")
      (node (ref "U$4") (pin "P$3") (pinfunction "P$3_P$3") (pintype "bidirectional"))
      (node (ref "U2") (pin "18") (pinfunction "CH11_18") (pintype "bidirectional"))
    )
    (net (code "31") (name "Net-(U2-CH12)") (class "Default")
      (node (ref "U$4") (pin "P$2") (pinfunction "P$2_P$2") (pintype "bidirectional"))
      (node (ref "U2") (pin "19") (pinfunction "CH12_19") (pintype "bidirectional"))
    )
    (net (code "32") (name "Net-(U2-CH13)") (class "Default")
      (node (ref "U$4") (pin "P$1") (pinfunction "P$1_P$1") (pintype "bidirectional"))
      (node (ref "U2") (pin "20") (pinfunction "CH13_20") (pintype "bidirectional"))
    )
    (net (code "33") (name "Net-(U3-RXLED)") (class "Default")
      (node (ref "LED1") (pin "C") (pinfunction "C_C") (pintype "passive"))
      (node (ref "U3") (pin "22") (pinfunction "RXLED_22") (pintype "input"))
    )
    (net (code "34") (name "Net-(U3-TXLED)") (class "Default")
      (node (ref "LED2") (pin "C") (pinfunction "C_C") (pintype "passive"))
      (node (ref "U3") (pin "23") (pinfunction "TXLED_23") (pintype "input"))
    )
    (net (code "35") (name "Net-(U5-SW)") (class "Default")
      (node (ref "L1") (pin "1") (pinfunction "1_1") (pintype "passive"))
      (node (ref "U5") (pin "5") (pinfunction "SW_5") (pintype "output"))
    )
    (net (code "36") (name "PWREN") (class "Default")
      (node (ref "U3") (pin "14") (pinfunction "PWREN_14") (pintype "input"))
    )
    (net (code "37") (name "RI") (class "Default")
      (node (ref "U3") (pin "6") (pinfunction "RI_6") (pintype "input"))
    )
    (net (code "38") (name "RTS") (class "Default")
      (node (ref "U3") (pin "3") (pinfunction "RTS_3") (pintype "output"))
    )
    (net (code "39") (name "RXD") (class "Default")
      (node (ref "U$2") (pin "P$11") (pinfunction "P$11_P$11") (pintype "bidirectional"))
      (node (ref "U3") (pin "5") (pinfunction "RXD_5") (pintype "input"))
    )
    (net (code "40") (name "SCL") (class "Default")
      (node (ref "JP1") (pin "5") (pinfunction "5_5") (pintype "passive"))
      (node (ref "JP1") (pin "6") (pinfunction "6_6") (pintype "passive"))
      (node (ref "R9") (pin "1") (pinfunction "1_1") (pintype "passive"))
      (node (ref "SHOULDER01") (pin "P$17") (pinfunction "P$17_P$17") (pintype "bidirectional"))
      (node (ref "SHOULDER02") (pin "P$17") (pinfunction "P$17_P$17") (pintype "bidirectional"))
      (node (ref "TO_SHOULDER01") (pin "P$17") (pinfunction "P$17_P$17") (pintype "bidirectional"))
      (node (ref "TO_SHOULDER02") (pin "P$17") (pinfunction "P$17_P$17") (pintype "bidirectional"))
      (node (ref "U$2") (pin "P$2") (pinfunction "P$2_P$2") (pintype "bidirectional"))
      (node (ref "U2") (pin "26") (pinfunction "SCL_26") (pintype "bidirectional"))
    )
    (net (code "41") (name "SDA") (class "Default")
      (node (ref "JP1") (pin "3") (pinfunction "3_3") (pintype "passive"))
      (node (ref "JP1") (pin "4") (pinfunction "4_4") (pintype "passive"))
      (node (ref "R8") (pin "1") (pinfunction "1_1") (pintype "passive"))
      (node (ref "SHOULDER01") (pin "P$16") (pinfunction "P$16_P$16") (pintype "bidirectional"))
      (node (ref "SHOULDER02") (pin "P$16") (pinfunction "P$16_P$16") (pintype "bidirectional"))
      (node (ref "TO_SHOULDER01") (pin "P$16") (pinfunction "P$16_P$16") (pintype "bidirectional"))
      (node (ref "TO_SHOULDER02") (pin "P$16") (pinfunction "P$16_P$16") (pintype "bidirectional"))
      (node (ref "U$2") (pin "P$1") (pinfunction "P$1_P$1") (pintype "bidirectional"))
      (node (ref "U2") (pin "27") (pinfunction "SDA_27") (pintype "bidirectional"))
    )
    (net (code "42") (name "SLEEP") (class "Default")
      (node (ref "U3") (pin "12") (pinfunction "SLEEP_12") (pintype "input"))
    )
    (net (code "43") (name "TXD") (class "Default")
      (node (ref "U$2") (pin "P$12") (pinfunction "P$12_P$12") (pintype "bidirectional"))
      (node (ref "U3") (pin "1") (pinfunction "TXD_1") (pintype "output"))
    )
    (net (code "44") (name "TXDEN") (class "Default")
      (node (ref "U3") (pin "13") (pinfunction "TXDEN_13") (pintype "input"))
    )
    (net (code "45") (name "V+") (class "Default")
      (node (ref "C10") (pin "1") (pinfunction "1_1") (pintype "passive"))
      (node (ref "C2") (pin "1") (pinfunction "1_1") (pintype "passive"))
      (node (ref "C4") (pin "1") (pinfunction "1_1") (pintype "passive"))
      (node (ref "C5") (pin "1") (pinfunction "1_1") (pintype "passive"))
      (node (ref "C6") (pin "1") (pinfunction "1_1") (pintype "passive"))
      (node (ref "C9") (pin "1") (pinfunction "1_1") (pintype "passive"))
      (node (ref "HIP01") (pin "P$10") (pinfunction "P$10_P$10") (pintype "bidirectional"))
      (node (ref "HIP01") (pin "P$12") (pinfunction "P$12_P$12") (pintype "bidirectional"))
      (node (ref "HIP02") (pin "P$10") (pinfunction "P$10_P$10") (pintype "bidirectional"))
      (node (ref "HIP02") (pin "P$12") (pinfunction "P$12_P$12") (pintype "bidirectional"))
      (node (ref "JP1") (pin "1") (pinfunction "1_1") (pintype "passive"))
      (node (ref "JP1") (pin "2") (pinfunction "2_2") (pintype "passive"))
      (node (ref "R3") (pin "1") (pinfunction "1_1") (pintype "passive"))
      (node (ref "SHOULDER01") (pin "P$10") (pinfunction "P$10_P$10") (pintype "bidirectional"))
      (node (ref "SHOULDER01") (pin "P$12") (pinfunction "P$12_P$12") (pintype "bidirectional"))
      (node (ref "SHOULDER02") (pin "P$10") (pinfunction "P$10_P$10") (pintype "bidirectional"))
      (node (ref "SHOULDER02") (pin "P$12") (pinfunction "P$12_P$12") (pintype "bidirectional"))
      (node (ref "TO_HIP01") (pin "P$10") (pinfunction "P$10_P$10") (pintype "bidirectional"))
      (node (ref "TO_HIP01") (pin "P$12") (pinfunction "P$12_P$12") (pintype "bidirectional"))
      (node (ref "TO_HIP02") (pin "P$10") (pinfunction "P$10_P$10") (pintype "bidirectional"))
      (node (ref "TO_HIP02") (pin "P$12") (pinfunction "P$12_P$12") (pintype "bidirectional"))
      (node (ref "TO_SHOULDER01") (pin "P$10") (pinfunction "P$10_P$10") (pintype "bidirectional"))
      (node (ref "TO_SHOULDER01") (pin "P$12") (pinfunction "P$12_P$12") (pintype "bidirectional"))
      (node (ref "TO_SHOULDER02") (pin "P$10") (pinfunction "P$10_P$10") (pintype "bidirectional"))
      (node (ref "TO_SHOULDER02") (pin "P$12") (pinfunction "P$12_P$12") (pintype "bidirectional"))
      (node (ref "U$3") (pin "VCC@1") (pinfunction "VCC_VCC@1") (pintype "power_in"))
      (node (ref "U$3") (pin "VCC@2") (pinfunction "VCC_VCC@2") (pintype "power_in"))
      (node (ref "U$3") (pin "VCC@3") (pinfunction "VCC_VCC@3") (pintype "power_in"))
      (node (ref "U$3") (pin "VCC@4") (pinfunction "VCC_VCC@4") (pintype "power_in"))
      (node (ref "U$3") (pin "VCC@5") (pinfunction "VCC_VCC@5") (pintype "power_in"))
      (node (ref "U$3") (pin "VCC@6") (pinfunction "VCC_VCC@6") (pintype "power_in"))
      (node (ref "U$3") (pin "VCC@7") (pinfunction "VCC_VCC@7") (pintype "power_in"))
      (node (ref "U$3") (pin "VCC@8") (pinfunction "VCC_VCC@8") (pintype "power_in"))
      (node (ref "U$4") (pin "VCC@1") (pinfunction "VCC_VCC@1") (pintype "power_in"))
      (node (ref "U$4") (pin "VCC@2") (pinfunction "VCC_VCC@2") (pintype "power_in"))
      (node (ref "U$4") (pin "VCC@3") (pinfunction "VCC_VCC@3") (pintype "power_in"))
      (node (ref "U$4") (pin "VCC@4") (pinfunction "VCC_VCC@4") (pintype "power_in"))
      (node (ref "U$4") (pin "VCC@5") (pinfunction "VCC_VCC@5") (pintype "power_in"))
      (node (ref "U$4") (pin "VCC@6") (pinfunction "VCC_VCC@6") (pintype "power_in"))
      (node (ref "U$8") (pin "2") (pinfunction "2_2") (pintype "passive"))
      (node (ref "U1") (pin "3") (pinfunction "VBAT_3") (pintype "power_in"))
      (node (ref "U5") (pin "1") (pinfunction "VIN_1") (pintype "power_in"))
    )
    (net (code "46") (name "V_USB") (class "Default")
      (node (ref "C17") (pin "A") (pinfunction "+_A") (pintype "passive"))
      (node (ref "C19") (pin "1") (pinfunction "1_1") (pintype "passive"))
      (node (ref "C8") (pin "1") (pinfunction "1_1") (pintype "passive"))
      (node (ref "J2") (pin "VBUS") (pinfunction "VBUS_VBUS") (pintype "power_in"))
      (node (ref "R1") (pin "2") (pinfunction "2_2") (pintype "passive"))
      (node (ref "R2") (pin "2") (pinfunction "2_2") (pintype "passive"))
      (node (ref "R4") (pin "1") (pinfunction "1_1") (pintype "passive"))
      (node (ref "U1") (pin "4") (pinfunction "VIN_4") (pintype "power_in"))
      (node (ref "U3") (pin "20") (pinfunction "VCC_20") (pintype "power_in"))
    )
    (net (code "47") (name "unconnected-(HIP01-PadP$1)") (class "Default")
      (node (ref "HIP01") (pin "P$1") (pinfunction "P$1_P$1") (pintype "bidirectional"))
    )
    (net (code "48") (name "unconnected-(HIP01-PadP$16)") (class "Default")
      (node (ref "HIP01") (pin "P$16") (pinfunction "P$16_P$16") (pintype "bidirectional"))
    )
    (net (code "49") (name "unconnected-(HIP01-PadP$17)") (class "Default")
      (node (ref "HIP01") (pin "P$17") (pinfunction "P$17_P$17") (pintype "bidirectional"))
    )
    (net (code "50") (name "unconnected-(HIP02-PadP$16)") (class "Default")
      (node (ref "HIP02") (pin "P$16") (pinfunction "P$16_P$16") (pintype "bidirectional"))
    )
    (net (code "51") (name "unconnected-(HIP02-PadP$17)") (class "Default")
      (node (ref "HIP02") (pin "P$17") (pinfunction "P$17_P$17") (pintype "bidirectional"))
    )
    (net (code "52") (name "unconnected-(J2-PadID)") (class "Default")
      (node (ref "J2") (pin "ID") (pinfunction "ID_ID") (pintype "bidirectional"))
    )
    (net (code "53") (name "unconnected-(TO_HIP01-PadP$1)") (class "Default")
      (node (ref "TO_HIP01") (pin "P$1") (pinfunction "P$1_P$1") (pintype "bidirectional"))
    )
    (net (code "54") (name "unconnected-(TO_HIP01-PadP$16)") (class "Default")
      (node (ref "TO_HIP01") (pin "P$16") (pinfunction "P$16_P$16") (pintype "bidirectional"))
    )
    (net (code "55") (name "unconnected-(TO_HIP01-PadP$17)") (class "Default")
      (node (ref "TO_HIP01") (pin "P$17") (pinfunction "P$17_P$17") (pintype "bidirectional"))
    )
    (net (code "56") (name "unconnected-(TO_HIP02-PadP$16)") (class "Default")
      (node (ref "TO_HIP02") (pin "P$16") (pinfunction "P$16_P$16") (pintype "bidirectional"))
    )
    (net (code "57") (name "unconnected-(TO_HIP02-PadP$17)") (class "Default")
      (node (ref "TO_HIP02") (pin "P$17") (pinfunction "P$17_P$17") (pintype "bidirectional"))
    )
    (net (code "58") (name "unconnected-(U$1-PadP$2)") (class "Default")
      (node (ref "U$1") (pin "P$2") (pinfunction "P$2_P$2") (pintype "bidirectional"))
    )
    (net (code "59") (name "unconnected-(U$1-PadP$3)") (class "Default")
      (node (ref "U$1") (pin "P$3") (pinfunction "P$3_P$3") (pintype "bidirectional"))
    )
    (net (code "60") (name "unconnected-(U$1-PadP$4)") (class "Default")
      (node (ref "U$1") (pin "P$4") (pinfunction "P$4_P$4") (pintype "bidirectional"))
    )
    (net (code "61") (name "unconnected-(U$1-PadP$5)") (class "Default")
      (node (ref "U$1") (pin "P$5") (pinfunction "P$5_P$5") (pintype "bidirectional"))
    )
    (net (code "62") (name "unconnected-(U$1-PadP$6)") (class "Default")
      (node (ref "U$1") (pin "P$6") (pinfunction "P$6_P$6") (pintype "bidirectional"))
    )
    (net (code "63") (name "unconnected-(U$1-PadP$7)") (class "Default")
      (node (ref "U$1") (pin "P$7") (pinfunction "P$7_P$7") (pintype "bidirectional"))
    )
    (net (code "64") (name "unconnected-(U$1-PadP$8)") (class "Default")
      (node (ref "U$1") (pin "P$8") (pinfunction "P$8_P$8") (pintype "bidirectional"))
    )
    (net (code "65") (name "unconnected-(U$1-PadP$9)") (class "Default")
      (node (ref "U$1") (pin "P$9") (pinfunction "P$9_P$9") (pintype "bidirectional"))
    )
    (net (code "66") (name "unconnected-(U$1-PadP$10)") (class "Default")
      (node (ref "U$1") (pin "P$10") (pinfunction "P$10_P$10") (pintype "bidirectional"))
    )
    (net (code "67") (name "unconnected-(U$1-PadP$11)") (class "Default")
      (node (ref "U$1") (pin "P$11") (pinfunction "P$11_P$11") (pintype "bidirectional"))
    )
    (net (code "68") (name "unconnected-(U$1-PadP$12)") (class "Default")
      (node (ref "U$1") (pin "P$12") (pinfunction "P$12_P$12") (pintype "bidirectional"))
    )
    (net (code "69") (name "unconnected-(U$1-PadP$13)") (class "Default")
      (node (ref "U$1") (pin "P$13") (pinfunction "P$13_P$13") (pintype "bidirectional"))
    )
    (net (code "70") (name "unconnected-(U$1-PadP$14)") (class "Default")
      (node (ref "U$1") (pin "P$14") (pinfunction "P$14_P$14") (pintype "bidirectional"))
    )
    (net (code "71") (name "unconnected-(U$1-PadP$15)") (class "Default")
      (node (ref "U$1") (pin "P$15") (pinfunction "P$15_P$15") (pintype "bidirectional"))
    )
    (net (code "72") (name "unconnected-(U$1-PadP$16)") (class "Default")
      (node (ref "U$1") (pin "P$16") (pinfunction "P$16_P$16") (pintype "bidirectional"))
    )
    (net (code "73") (name "unconnected-(U$2-PadP$3)") (class "Default")
      (node (ref "U$2") (pin "P$3") (pinfunction "P$3_P$3") (pintype "bidirectional"))
    )
    (net (code "74") (name "unconnected-(U$2-PadP$4)") (class "Default")
      (node (ref "U$2") (pin "P$4") (pinfunction "P$4_P$4") (pintype "bidirectional"))
    )
    (net (code "75") (name "unconnected-(U$2-PadP$5)") (class "Default")
      (node (ref "U$2") (pin "P$5") (pinfunction "P$5_P$5") (pintype "bidirectional"))
    )
    (net (code "76") (name "unconnected-(U$2-PadP$6)") (class "Default")
      (node (ref "U$2") (pin "P$6") (pinfunction "P$6_P$6") (pintype "bidirectional"))
    )
    (net (code "77") (name "unconnected-(U$2-PadP$7)") (class "Default")
      (node (ref "U$2") (pin "P$7") (pinfunction "P$7_P$7") (pintype "bidirectional"))
    )
    (net (code "78") (name "unconnected-(U$2-PadP$8)") (class "Default")
      (node (ref "U$2") (pin "P$8") (pinfunction "P$8_P$8") (pintype "bidirectional"))
    )
    (net (code "79") (name "unconnected-(U$2-PadP$9)") (class "Default")
      (node (ref "U$2") (pin "P$9") (pinfunction "P$9_P$9") (pintype "bidirectional"))
    )
    (net (code "80") (name "unconnected-(U$2-PadP$13)") (class "Default")
      (node (ref "U$2") (pin "P$13") (pinfunction "P$13_P$13") (pintype "bidirectional"))
    )
    (net (code "81") (name "unconnected-(U$2-PadP$14)") (class "Default")
      (node (ref "U$2") (pin "P$14") (pinfunction "P$14_P$14") (pintype "bidirectional"))
    )
    (net (code "82") (name "unconnected-(U2-CH14-Pad21)") (class "Default")
      (node (ref "U2") (pin "21") (pinfunction "CH14_21") (pintype "bidirectional"))
    )
    (net (code "83") (name "unconnected-(U2-CH15-Pad22)") (class "Default")
      (node (ref "U2") (pin "22") (pinfunction "CH15_22") (pintype "bidirectional"))
    )
    (net (code "84") (name "unconnected-(U3-OSCI-Pad27)") (class "Default")
      (node (ref "U3") (pin "27") (pinfunction "OSCI_27") (pintype "input"))
    )
    (net (code "85") (name "unconnected-(U3-OSCO-Pad28)") (class "Default")
      (node (ref "U3") (pin "28") (pinfunction "OSCO_28") (pintype "output"))
    )
    (net (code "86") (name "unconnected-(U3-RESET-Pad19)") (class "Default")
      (node (ref "U3") (pin "19") (pinfunction "RESET_19") (pintype "input"))
    )
  )
)
